# 130816_I_T_V_AriloRX_0_0.net
KiCad netlist of a schematic drawn in EAGLE
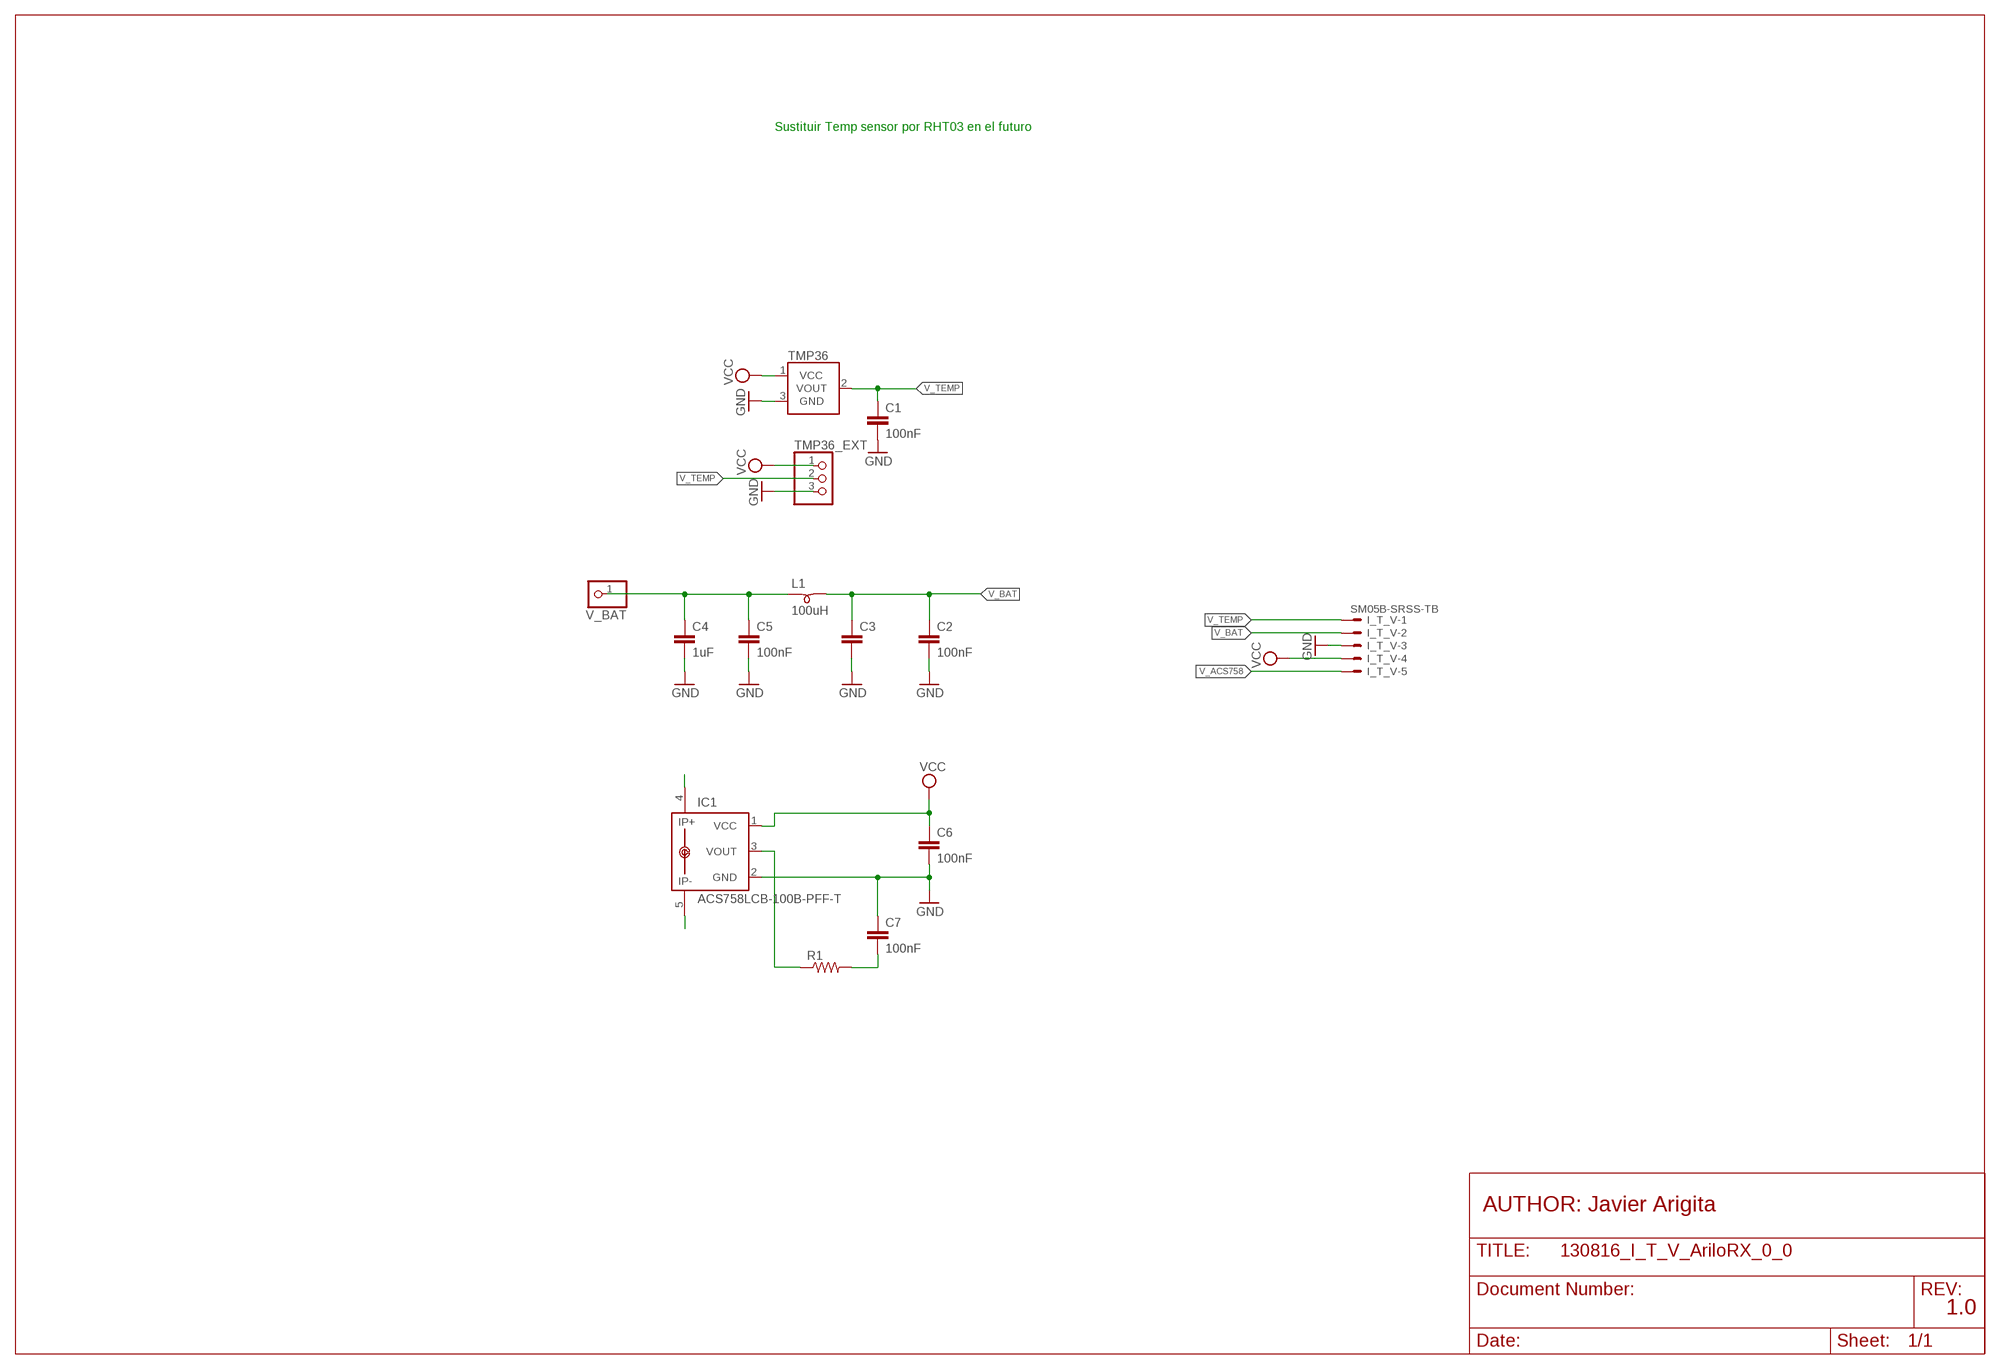
[diagram p0: schematic, sheet 1]

(export (version "E")
  (design (tool "Eeschema 10.0.6"))
  (components
    (comp (ref "C1")
      (value "100nF")
      (footprint "eagle-import:C0805")
      (libsource (lib "eagle-import") (part "C-EUC0805"))
    )
    (comp (ref "C2")
      (value "100nF")
      (footprint "eagle-import:C0805")
      (libsource (lib "eagle-import") (part "C-EUC0805"))
    )
    (comp (ref "C3")
      (value "C-EUC3216")
      (footprint "eagle-import:C3216")
      (libsource (lib "eagle-import") (part "C-EUC3216"))
    )
    (comp (ref "C4")
      (value "1uF")
      (footprint "eagle-import:C3216")
      (libsource (lib "eagle-import") (part "C-EUC3216"))
    )
    (comp (ref "C5")
      (value "100nF")
      (footprint "eagle-import:C0805")
      (libsource (lib "eagle-import") (part "C-EUC0805"))
    )
    (comp (ref "C6")
      (value "100nF")
      (footprint "eagle-import:C0805")
      (libsource (lib "eagle-import") (part "C-EUC0805"))
    )
    (comp (ref "C7")
      (value "100nF")
      (footprint "eagle-import:C0805")
      (libsource (lib "eagle-import") (part "C-EUC0805"))
    )
    (comp (ref "IC1")
      (value "ACS758LCB-100B-PFF-T")
      (footprint "eagle-import:CB-PFF")
      (libsource (lib "eagle-import") (part "ACS758LCB-100B-PFF-T"))
    )
    (comp (ref "I_T_V")
      (value "SM05B-SRSS-TB")
      (footprint "eagle-import:SM05B-SRSS-TB")
      (libsource (lib "eagle-import") (part "?M05B-SRSS-TBS"))
    )
    (comp (ref "L1")
      (value "100uH")
      (footprint "eagle-import:SM-B5")
      (libsource (lib "eagle-import") (part "SM-B5"))
    )
    (comp (ref "R1")
      (value "RESISTOR0805")
      (footprint "eagle-import:R0805")
      (libsource (lib "eagle-import") (part "RESISTOR0805"))
    )
    (comp (ref "TMP36")
      (value "TMP36GT9")
      (footprint "eagle-import:TO-92")
      (libsource (lib "eagle-import") (part "TMP36GT9"))
    )
    (comp (ref "TMP36_EXT")
      (value "PINHD-1X3")
      (footprint "eagle-import:1X03")
      (libsource (lib "eagle-import") (part "PINHD-1X3"))
    )
    (comp (ref "V_BAT")
      (value "PINHD-1X1")
      (footprint "eagle-import:1X01")
      (libsource (lib "eagle-import") (part "PINHD-1X1"))
    )
  )
  (nets
    (net (code "1") (name "GND") (class "Default")
      (node (ref "C1") (pin "2") (pinfunction "2_2") (pintype "passive"))
      (node (ref "C2") (pin "2") (pinfunction "2_2") (pintype "passive"))
      (node (ref "C3") (pin "2") (pinfunction "2_2") (pintype "passive"))
      (node (ref "C4") (pin "2") (pinfunction "2_2") (pintype "passive"))
      (node (ref "C5") (pin "2") (pinfunction "2_2") (pintype "passive"))
      (node (ref "C6") (pin "2") (pinfunction "2_2") (pintype "passive"))
      (node (ref "C7") (pin "1") (pinfunction "1_1") (pintype "passive"))
      (node (ref "IC1") (pin "2") (pinfunction "GND_2") (pintype "power_in"))
      (node (ref "I_T_V") (pin "3") (pinfunction "S_3") (pintype "passive"))
      (node (ref "TMP36") (pin "3") (pinfunction "GND_3") (pintype "bidirectional"))
      (node (ref "TMP36_EXT") (pin "3") (pinfunction "3_3") (pintype "passive"))
    )
    (net (code "2") (name "Net-(C4-Pad1)") (class "Default")
      (node (ref "C4") (pin "1") (pinfunction "1_1") (pintype "passive"))
      (node (ref "C5") (pin "1") (pinfunction "1_1") (pintype "passive"))
      (node (ref "L1") (pin "1") (pinfunction "1_1") (pintype "passive"))
      (node (ref "V_BAT") (pin "1") (pinfunction "1_1") (pintype "passive"))
    )
    (net (code "3") (name "Net-(C7-Pad2)") (class "Default")
      (node (ref "C7") (pin "2") (pinfunction "2_2") (pintype "passive"))
      (node (ref "R1") (pin "2") (pinfunction "2_2") (pintype "passive"))
    )
    (net (code "4") (name "Net-(IC1-VOUT)") (class "Default")
      (node (ref "IC1") (pin "3") (pinfunction "VOUT_3") (pintype "output"))
      (node (ref "R1") (pin "1") (pinfunction "1_1") (pintype "passive"))
    )
    (net (code "5") (name "VCC") (class "Default")
      (node (ref "C6") (pin "1") (pinfunction "1_1") (pintype "passive"))
      (node (ref "IC1") (pin "1") (pinfunction "VCC_1") (pintype "power_in"))
      (node (ref "I_T_V") (pin "4") (pinfunction "S_4") (pintype "passive"))
      (node (ref "TMP36") (pin "1") (pinfunction "VCC_1") (pintype "bidirectional"))
      (node (ref "TMP36_EXT") (pin "1") (pinfunction "1_1") (pintype "passive"))
    )
    (net (code "6") (name "V_ACS758") (class "Default")
      (node (ref "I_T_V") (pin "5") (pinfunction "S_5") (pintype "passive"))
    )
    (net (code "7") (name "V_BAT") (class "Default")
      (node (ref "C2") (pin "1") (pinfunction "1_1") (pintype "passive"))
      (node (ref "C3") (pin "1") (pinfunction "1_1") (pintype "passive"))
      (node (ref "I_T_V") (pin "2") (pinfunction "S_2") (pintype "passive"))
      (node (ref "L1") (pin "2") (pinfunction "2_2") (pintype "passive"))
    )
    (net (code "8") (name "V_TEMP") (class "Default")
      (node (ref "C1") (pin "1") (pinfunction "1_1") (pintype "passive"))
      (node (ref "I_T_V") (pin "1") (pinfunction "S_1") (pintype "passive"))
      (node (ref "TMP36") (pin "2") (pinfunction "VOUT_2") (pintype "bidirectional"))
      (node (ref "TMP36_EXT") (pin "2") (pinfunction "2_2") (pintype "passive"))
    )
    (net (code "9") (name "unconnected-(IC1-IP+-Pad4)") (class "Default")
      (node (ref "IC1") (pin "4") (pinfunction "IP+_4") (pintype "passive"))
    )
    (net (code "10") (name "unconnected-(IC1-IP--Pad5)") (class "Default")
      (node (ref "IC1") (pin "5") (pinfunction "IP-_5") (pintype "passive"))
    )
    (net (code "11") (name "unconnected-(IC1-PadIP+1)") (class "Default")
      (node (ref "IC1") (pin "IP+1") (pinfunction "IP+1_IP+1") (pintype "input"))
    )
    (net (code "12") (name "unconnected-(IC1-PadIP-1)") (class "Default")
      (node (ref "IC1") (pin "IP-1") (pinfunction "IP-1_IP-1") (pintype "input"))
    )
  )
)
